# top.net
KiCad netlist of a schematic drawn in Altium Designer
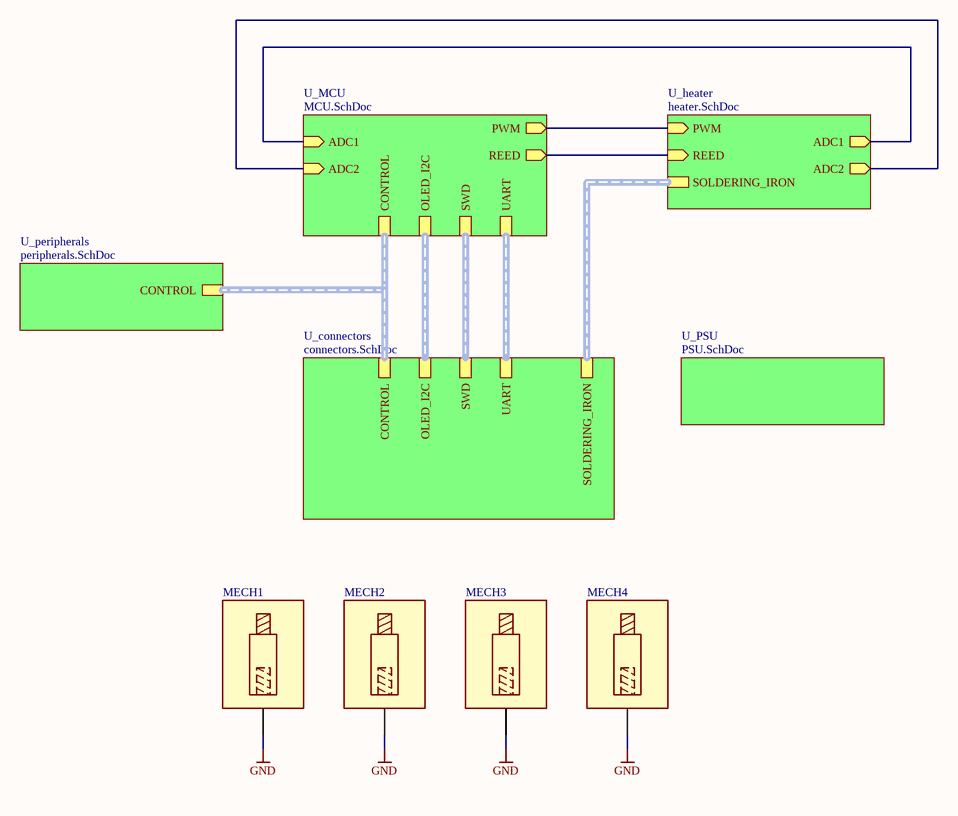
[diagram p0: top.SchDoc]

(export (version "E")
  (design (tool "Eeschema 10.0.6"))
  (components
    (comp (ref "MECH1")
      (value "M3X0.5")
      (footprint "MECH_SPACER_MALE_FEMALE_18MM_M3")
      (fields
        (field (name "PART NUMBER") "MECH_SPACER_MALE_FEMALE_18MM_M3")
        (field (name "MANUFACTURER") "FIX&FASTEN")
        (field (name "MANUFACTURER PART NUMBER") "TP-18")
      )
      (libsource (lib "Library") (part "MECH_SPACER_MALE_FEMALE"))
    )
    (comp (ref "MECH2")
      (value "M3X0.5")
      (footprint "MECH_SPACER_MALE_FEMALE_18MM_M3")
      (fields
        (field (name "PART NUMBER") "MECH_SPACER_MALE_FEMALE_18MM_M3")
        (field (name "MANUFACTURER") "FIX&FASTEN")
        (field (name "MANUFACTURER PART NUMBER") "TP-18")
      )
      (libsource (lib "Library") (part "MECH_SPACER_MALE_FEMALE"))
    )
    (comp (ref "MECH3")
      (value "M3X0.5")
      (footprint "MECH_SPACER_MALE_FEMALE_18MM_M3")
      (fields
        (field (name "PART NUMBER") "MECH_SPACER_MALE_FEMALE_18MM_M3")
        (field (name "MANUFACTURER") "FIX&FASTEN")
        (field (name "MANUFACTURER PART NUMBER") "TP-18")
      )
      (libsource (lib "Library") (part "MECH_SPACER_MALE_FEMALE"))
    )
    (comp (ref "MECH4")
      (value "M3X0.5")
      (footprint "MECH_SPACER_MALE_FEMALE_18MM_M3")
      (fields
        (field (name "PART NUMBER") "MECH_SPACER_MALE_FEMALE_18MM_M3")
        (field (name "MANUFACTURER") "FIX&FASTEN")
        (field (name "MANUFACTURER PART NUMBER") "TP-18")
      )
      (libsource (lib "Library") (part "MECH_SPACER_MALE_FEMALE"))
    )
  )
  (nets
    (net (code "10") (name "GND") (class "Default")
      (node (ref "MECH1") (pin "1") (pintype "passive"))
      (node (ref "MECH2") (pin "1") (pintype "passive"))
      (node (ref "MECH3") (pin "1") (pintype "passive"))
      (node (ref "MECH4") (pin "1") (pintype "passive"))
    )
  )
)
